# Sheet2.net
KiCad netlist of a schematic drawn in Altium Designer
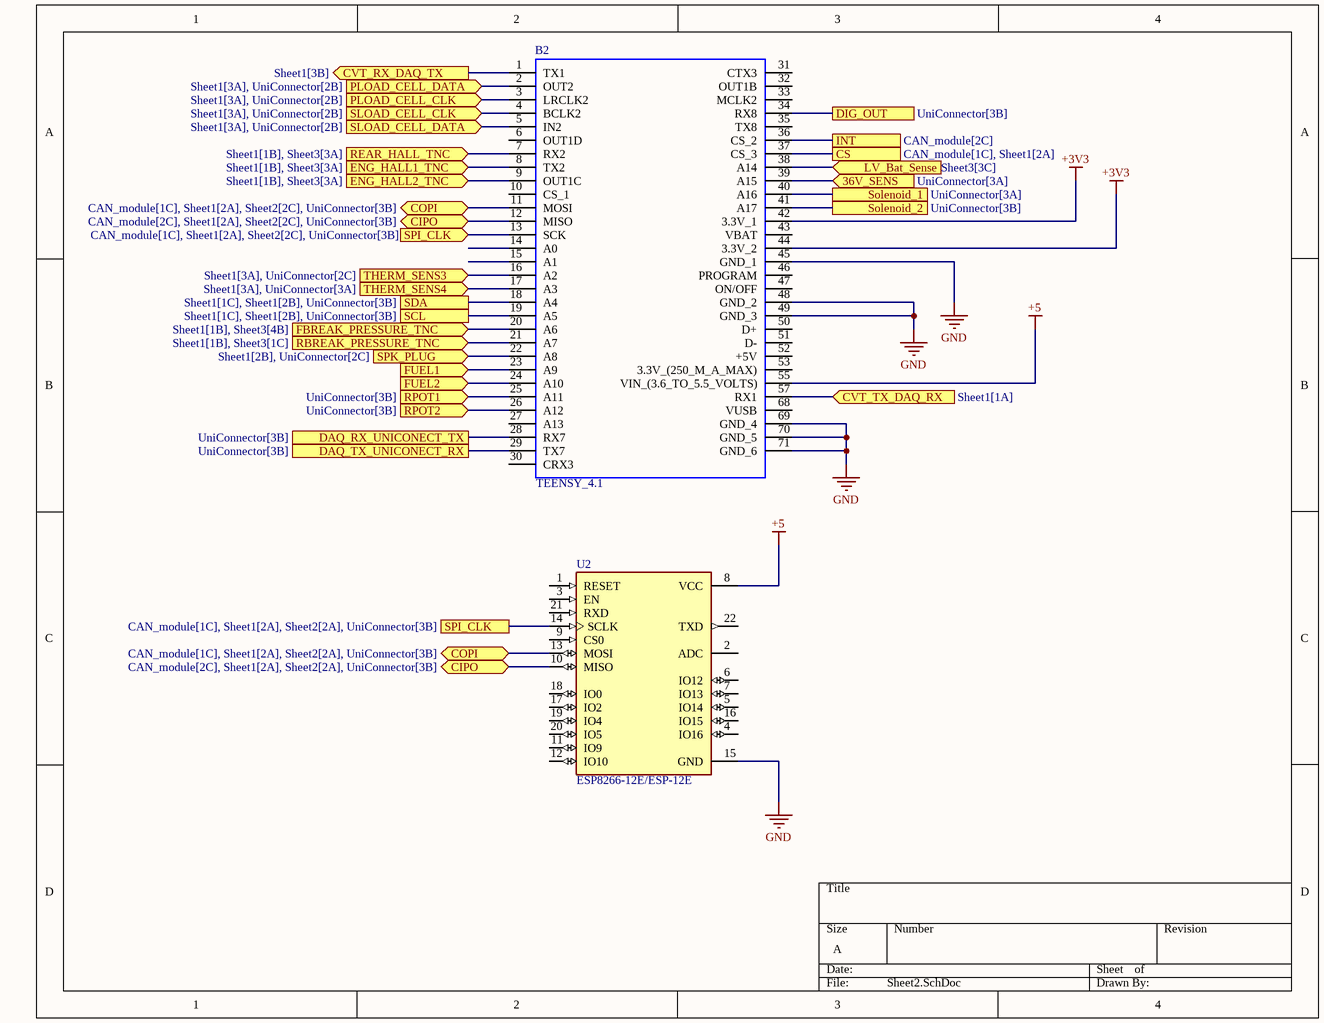
[diagram p0: Sheet2.SchDoc]

(export (version "E")
  (design (tool "Eeschema 10.0.6"))
  (components
    (comp (ref "B2")
      (value "TEENSY_4.1")
      (footprint "TEENSY41")
      (description "Teensy 4.1 Development Board")
      (fields (field (name "MANUFACTURER_PART_NUMBER") "TEENSY 4.1"))
      (libsource (lib "TEENSY_4.1") (part "TEENSY_4.1"))
    )
    (comp (ref "U2")
      (value "ESP8266-12E/ESP-12E")
      (footprint "XCVR_ESP8266-12E/ESP-12E")
      (fields (field (name "MF") "AI-Thinker"))
      (libsource (lib "ESP8266-12E_ESP-12E") (part "ESP8266-12E/ESP-12E"))
    )
  )
  (nets
    (net (code "1") (name "+3V3") (class "Default")
      (node (ref "B2") (pin "42") (pinfunction "3.3V_1_42") (pintype "passive"))
      (node (ref "B2") (pin "44") (pinfunction "3.3V_2_44") (pintype "passive"))
    )
    (net (code "2") (name "+5") (class "Default")
      (node (ref "B2") (pin "55") (pinfunction "VIN_(3.6_TO_5.5_VOLTS)_55") (pintype "passive"))
      (node (ref "U2") (pin "8") (pinfunction "VCC_8") (pintype "power_in"))
    )
    (net (code "3") (name "/36V_SENS") (class "Default")
      (node (ref "B2") (pin "39") (pinfunction "A15_39") (pintype "passive"))
    )
    (net (code "4") (name "/CIPO") (class "Default")
      (node (ref "B2") (pin "12") (pinfunction "MISO_12") (pintype "passive"))
      (node (ref "U2") (pin "10") (pinfunction "MISO_10") (pintype "bidirectional"))
    )
    (net (code "5") (name "/COPI") (class "Default")
      (node (ref "B2") (pin "11") (pinfunction "MOSI_11") (pintype "passive"))
      (node (ref "U2") (pin "13") (pinfunction "MOSI_13") (pintype "bidirectional"))
    )
    (net (code "6") (name "/CS") (class "Default")
      (node (ref "B2") (pin "37") (pinfunction "CS_3_37") (pintype "passive"))
    )
    (net (code "7") (name "/CVT_RX_DAQ_TX") (class "Default")
      (node (ref "B2") (pin "1") (pinfunction "TX1_1") (pintype "passive"))
    )
    (net (code "8") (name "/CVT_TX_DAQ_RX") (class "Default")
      (node (ref "B2") (pin "57") (pinfunction "RX1_57") (pintype "passive"))
    )
    (net (code "9") (name "/DAQ_RX_UNICONECT_TX") (class "Default")
      (node (ref "B2") (pin "28") (pinfunction "RX7_28") (pintype "passive"))
    )
    (net (code "10") (name "/DAQ_TX_UNICONECT_RX") (class "Default")
      (node (ref "B2") (pin "29") (pinfunction "TX7_29") (pintype "passive"))
    )
    (net (code "11") (name "/DIG_OUT") (class "Default")
      (node (ref "B2") (pin "34") (pinfunction "RX8_34") (pintype "passive"))
    )
    (net (code "12") (name "/ENG_HALL1_TNC") (class "Default")
      (node (ref "B2") (pin "8") (pinfunction "TX2_8") (pintype "passive"))
    )
    (net (code "13") (name "/ENG_HALL2_TNC") (class "Default")
      (node (ref "B2") (pin "9") (pinfunction "OUT1C_9") (pintype "passive"))
    )
    (net (code "14") (name "/FBREAK_PRESSURE_TNC") (class "Default")
      (node (ref "B2") (pin "20") (pinfunction "A6_20") (pintype "passive"))
    )
    (net (code "15") (name "/FUEL1") (class "Default")
      (node (ref "B2") (pin "23") (pinfunction "A9_23") (pintype "passive"))
    )
    (net (code "16") (name "/FUEL2") (class "Default")
      (node (ref "B2") (pin "24") (pinfunction "A10_24") (pintype "passive"))
    )
    (net (code "17") (name "/INT") (class "Default")
      (node (ref "B2") (pin "36") (pinfunction "CS_2_36") (pintype "passive"))
    )
    (net (code "18") (name "/LV_Bat_Sense") (class "Default")
      (node (ref "B2") (pin "38") (pinfunction "A14_38") (pintype "passive"))
    )
    (net (code "19") (name "/PLOAD_CELL_CLK") (class "Default")
      (node (ref "B2") (pin "3") (pinfunction "LRCLK2_3") (pintype "passive"))
    )
    (net (code "20") (name "/PLOAD_CELL_DATA") (class "Default")
      (node (ref "B2") (pin "2") (pinfunction "OUT2_2") (pintype "passive"))
    )
    (net (code "21") (name "/RBREAK_PRESSURE_TNC") (class "Default")
      (node (ref "B2") (pin "21") (pinfunction "A7_21") (pintype "passive"))
    )
    (net (code "22") (name "/REAR_HALL_TNC") (class "Default")
      (node (ref "B2") (pin "7") (pinfunction "RX2_7") (pintype "passive"))
    )
    (net (code "23") (name "/RPOT1") (class "Default")
      (node (ref "B2") (pin "25") (pinfunction "A11_25") (pintype "passive"))
    )
    (net (code "24") (name "/RPOT2") (class "Default")
      (node (ref "B2") (pin "26") (pinfunction "A12_26") (pintype "passive"))
    )
    (net (code "25") (name "/SCL") (class "Default")
      (node (ref "B2") (pin "19") (pinfunction "A5_19") (pintype "passive"))
    )
    (net (code "26") (name "/SDA") (class "Default")
      (node (ref "B2") (pin "18") (pinfunction "A4_18") (pintype "passive"))
    )
    (net (code "27") (name "/SLOAD_CELL_CLK") (class "Default")
      (node (ref "B2") (pin "4") (pinfunction "BCLK2_4") (pintype "passive"))
    )
    (net (code "28") (name "/SLOAD_CELL_DATA") (class "Default")
      (node (ref "B2") (pin "5") (pinfunction "IN2_5") (pintype "passive"))
    )
    (net (code "29") (name "/SPI_CLK") (class "Default")
      (node (ref "B2") (pin "13") (pinfunction "SCK_13") (pintype "passive"))
      (node (ref "U2") (pin "14") (pinfunction "SCLK_14") (pintype "input"))
    )
    (net (code "30") (name "/SPK_PLUG") (class "Default")
      (node (ref "B2") (pin "22") (pinfunction "A8_22") (pintype "passive"))
    )
    (net (code "31") (name "/Solenoid_1") (class "Default")
      (node (ref "B2") (pin "40") (pinfunction "A16_40") (pintype "passive"))
    )
    (net (code "32") (name "/Solenoid_2") (class "Default")
      (node (ref "B2") (pin "41") (pinfunction "A17_41") (pintype "passive"))
    )
    (net (code "33") (name "/THERM_SENS3") (class "Default")
      (node (ref "B2") (pin "16") (pinfunction "A2_16") (pintype "passive"))
    )
    (net (code "34") (name "/THERM_SENS4") (class "Default")
      (node (ref "B2") (pin "17") (pinfunction "A3_17") (pintype "passive"))
    )
    (net (code "35") (name "GND") (class "Default")
      (node (ref "B2") (pin "45") (pinfunction "GND_1_45") (pintype "passive"))
      (node (ref "B2") (pin "48") (pinfunction "GND_2_48") (pintype "passive"))
      (node (ref "B2") (pin "49") (pinfunction "GND_3_49") (pintype "passive"))
      (node (ref "B2") (pin "69") (pinfunction "GND_4_69") (pintype "passive"))
      (node (ref "B2") (pin "70") (pinfunction "GND_5_70") (pintype "passive"))
      (node (ref "B2") (pin "71") (pinfunction "GND_6_71") (pintype "passive"))
      (node (ref "U2") (pin "15") (pinfunction "GND_15") (pintype "power_in"))
    )
    (net (code "36") (name "unconnected-(B2-+5V-Pad52)") (class "Default")
      (node (ref "B2") (pin "52") (pinfunction "+5V_52") (pintype "passive"))
    )
    (net (code "37") (name "unconnected-(B2-3.3V_(250_M_A_MAX)-Pad53)") (class "Default")
      (node (ref "B2") (pin "53") (pinfunction "3.3V_(250_M_A_MAX)_53") (pintype "passive"))
    )
    (net (code "38") (name "unconnected-(B2-A0-Pad14)") (class "Default")
      (node (ref "B2") (pin "14") (pinfunction "A0_14") (pintype "passive"))
    )
    (net (code "39") (name "unconnected-(B2-A1-Pad15)") (class "Default")
      (node (ref "B2") (pin "15") (pinfunction "A1_15") (pintype "passive"))
    )
    (net (code "40") (name "unconnected-(B2-A13-Pad27)") (class "Default")
      (node (ref "B2") (pin "27") (pinfunction "A13_27") (pintype "passive"))
    )
    (net (code "41") (name "unconnected-(B2-CRX3-Pad30)") (class "Default")
      (node (ref "B2") (pin "30") (pinfunction "CRX3_30") (pintype "passive"))
    )
    (net (code "42") (name "unconnected-(B2-CS_1-Pad10)") (class "Default")
      (node (ref "B2") (pin "10") (pinfunction "CS_1_10") (pintype "passive"))
    )
    (net (code "43") (name "unconnected-(B2-CTX3-Pad31)") (class "Default")
      (node (ref "B2") (pin "31") (pinfunction "CTX3_31") (pintype "passive"))
    )
    (net (code "44") (name "unconnected-(B2-D+-Pad50)") (class "Default")
      (node (ref "B2") (pin "50") (pinfunction "D+_50") (pintype "passive"))
    )
    (net (code "45") (name "unconnected-(B2-D--Pad51)") (class "Default")
      (node (ref "B2") (pin "51") (pinfunction "D-_51") (pintype "passive"))
    )
    (net (code "46") (name "unconnected-(B2-MCLK2-Pad33)") (class "Default")
      (node (ref "B2") (pin "33") (pinfunction "MCLK2_33") (pintype "passive"))
    )
    (net (code "47") (name "unconnected-(B2-ON{slash}OFF-Pad47)") (class "Default")
      (node (ref "B2") (pin "47") (pinfunction "ON/OFF_47") (pintype "passive"))
    )
    (net (code "48") (name "unconnected-(B2-OUT1B-Pad32)") (class "Default")
      (node (ref "B2") (pin "32") (pinfunction "OUT1B_32") (pintype "passive"))
    )
    (net (code "49") (name "unconnected-(B2-OUT1D-Pad6)") (class "Default")
      (node (ref "B2") (pin "6") (pinfunction "OUT1D_6") (pintype "passive"))
    )
    (net (code "50") (name "unconnected-(B2-PROGRAM-Pad46)") (class "Default")
      (node (ref "B2") (pin "46") (pinfunction "PROGRAM_46") (pintype "passive"))
    )
    (net (code "51") (name "unconnected-(B2-TX8-Pad35)") (class "Default")
      (node (ref "B2") (pin "35") (pinfunction "TX8_35") (pintype "passive"))
    )
    (net (code "52") (name "unconnected-(B2-VBAT-Pad43)") (class "Default")
      (node (ref "B2") (pin "43") (pinfunction "VBAT_43") (pintype "passive"))
    )
    (net (code "53") (name "unconnected-(B2-VUSB-Pad68)") (class "Default")
      (node (ref "B2") (pin "68") (pinfunction "VUSB_68") (pintype "passive"))
    )
    (net (code "54") (name "unconnected-(U2-ADC-Pad2)") (class "Default")
      (node (ref "U2") (pin "2") (pinfunction "ADC_2") (pintype "passive"))
    )
    (net (code "55") (name "unconnected-(U2-CS0-Pad9)") (class "Default")
      (node (ref "U2") (pin "9") (pinfunction "CS0_9") (pintype "input"))
    )
    (net (code "56") (name "unconnected-(U2-EN-Pad3)") (class "Default")
      (node (ref "U2") (pin "3") (pinfunction "EN_3") (pintype "input"))
    )
    (net (code "57") (name "unconnected-(U2-IO0-Pad18)") (class "Default")
      (node (ref "U2") (pin "18") (pinfunction "IO0_18") (pintype "bidirectional"))
    )
    (net (code "58") (name "unconnected-(U2-IO2-Pad17)") (class "Default")
      (node (ref "U2") (pin "17") (pinfunction "IO2_17") (pintype "bidirectional"))
    )
    (net (code "59") (name "unconnected-(U2-IO4-Pad19)") (class "Default")
      (node (ref "U2") (pin "19") (pinfunction "IO4_19") (pintype "bidirectional"))
    )
    (net (code "60") (name "unconnected-(U2-IO5-Pad20)") (class "Default")
      (node (ref "U2") (pin "20") (pinfunction "IO5_20") (pintype "bidirectional"))
    )
    (net (code "61") (name "unconnected-(U2-IO9-Pad11)") (class "Default")
      (node (ref "U2") (pin "11") (pinfunction "IO9_11") (pintype "bidirectional"))
    )
    (net (code "62") (name "unconnected-(U2-IO10-Pad12)") (class "Default")
      (node (ref "U2") (pin "12") (pinfunction "IO10_12") (pintype "bidirectional"))
    )
    (net (code "63") (name "unconnected-(U2-IO12-Pad6)") (class "Default")
      (node (ref "U2") (pin "6") (pinfunction "IO12_6") (pintype "bidirectional"))
    )
    (net (code "64") (name "unconnected-(U2-IO13-Pad7)") (class "Default")
      (node (ref "U2") (pin "7") (pinfunction "IO13_7") (pintype "bidirectional"))
    )
    (net (code "65") (name "unconnected-(U2-IO14-Pad5)") (class "Default")
      (node (ref "U2") (pin "5") (pinfunction "IO14_5") (pintype "bidirectional"))
    )
    (net (code "66") (name "unconnected-(U2-IO15-Pad16)") (class "Default")
      (node (ref "U2") (pin "16") (pinfunction "IO15_16") (pintype "bidirectional"))
    )
    (net (code "67") (name "unconnected-(U2-IO16-Pad4)") (class "Default")
      (node (ref "U2") (pin "4") (pinfunction "IO16_4") (pintype "bidirectional"))
    )
    (net (code "68") (name "unconnected-(U2-RESET-Pad1)") (class "Default")
      (node (ref "U2") (pin "1") (pinfunction "RESET_1") (pintype "input"))
    )
    (net (code "69") (name "unconnected-(U2-RXD-Pad21)") (class "Default")
      (node (ref "U2") (pin "21") (pinfunction "RXD_21") (pintype "input"))
    )
    (net (code "70") (name "unconnected-(U2-TXD-Pad22)") (class "Default")
      (node (ref "U2") (pin "22") (pinfunction "TXD_22") (pintype "output"))
    )
  )
)
